# V02.net
KiCad netlist of a schematic drawn in Altium Designer
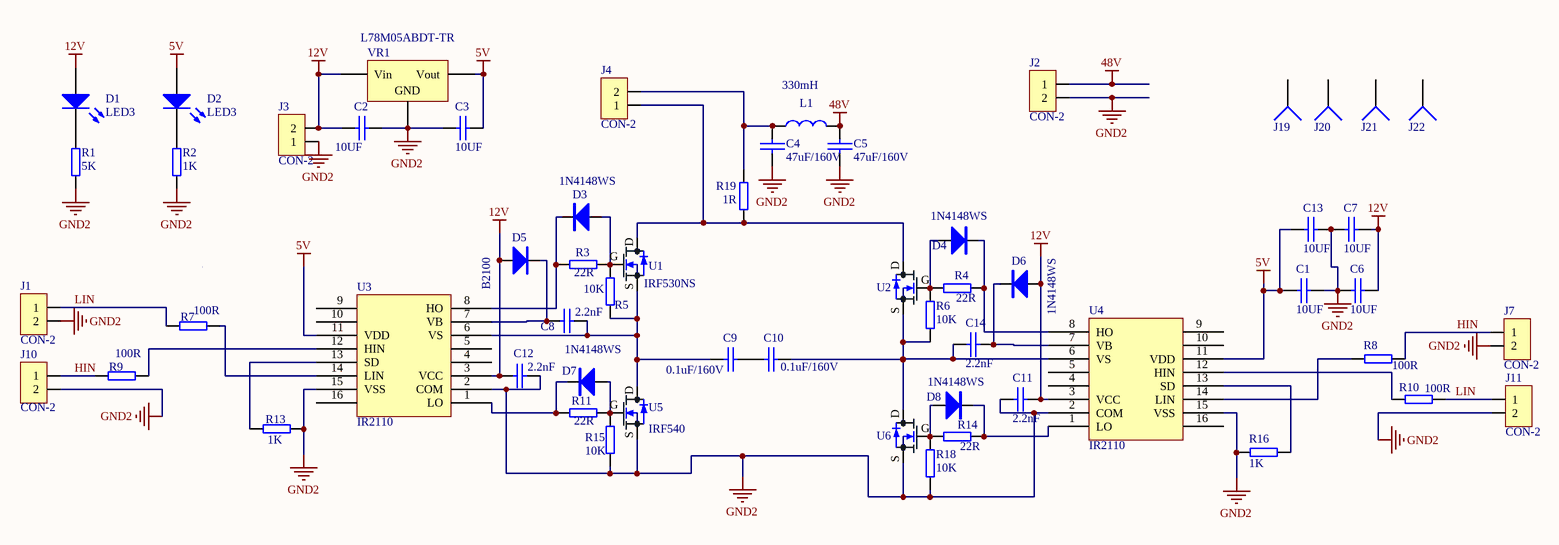
[diagram p0: 发送端V02.SchDoc]

(export (version "E")
  (design (tool "Eeschema 10.0.6"))
  (components
    (comp (ref "C1") (value "10UF") (footprint "1206_C") (libsource (lib "WegeV1") (part "CAP")))
    (comp (ref "C2") (value "10UF") (footprint "1206_C") (libsource (lib "WegeV1") (part "CAP")))
    (comp (ref "C3") (value "10UF") (footprint "1206_C") (libsource (lib "WegeV1") (part "CAP")))
    (comp (ref "C4") (value "47uF/160V") (footprint "C3618") (libsource (lib "WegeV1") (part "CAP")))
    (comp (ref "C5") (value "47uF/160V") (footprint "C3618") (libsource (lib "WegeV1") (part "CAP")))
    (comp (ref "C6") (value "10UF") (footprint "1206_C") (libsource (lib "WegeV1") (part "CAP")))
    (comp (ref "C7") (value "10UF") (footprint "1206_C") (libsource (lib "WegeV1") (part "CAP")))
    (comp (ref "C8") (value "2.2nF") (footprint "1206_C") (libsource (lib "WegeV1") (part "CAP")))
    (comp (ref "C9") (value "0.1uF/160V") (footprint "DSMC82") (libsource (lib "WegeV1") (part "CAP")))
    (comp (ref "C10") (value "0.1uF/160V") (footprint "DSMC82") (libsource (lib "WegeV1") (part "CAP")))
    (comp (ref "C11") (value "2.2nF") (footprint "1206_C") (libsource (lib "WegeV1") (part "CAP")))
    (comp (ref "C12") (value "2.2nF") (footprint "1206_C") (libsource (lib "WegeV1") (part "CAP")))
    (comp (ref "C13") (value "10UF") (footprint "1206_C") (libsource (lib "WegeV1") (part "CAP")))
    (comp (ref "C14") (value "2.2nF") (footprint "1206_C") (libsource (lib "WegeV1") (part "CAP")))
    (comp (ref "D1")
      (value "LED3")
      (footprint "1206_R")
      (description "Typical BLUE SiC LED")
      (fields (field (name "PUBLISHER") "Altium Limited"))
      (libsource (lib "Miscellaneous Devices") (part "LED3"))
    )
    (comp (ref "D2")
      (value "LED3")
      (footprint "1206_R")
      (description "Typical BLUE SiC LED")
      (fields (field (name "PUBLISHER") "Altium Limited"))
      (libsource (lib "Miscellaneous Devices") (part "LED3"))
    )
    (comp (ref "D3")
      (value "1N4148WS")
      (footprint "SOD-123")
      (description "1N4148WS IN4148 0805 SOD323 丝印T4 贴片开关二极管")
      (libsource (lib "WegeV1") (part "1N4148"))
    )
    (comp (ref "D4")
      (value "1N4148WS")
      (footprint "SOD-123")
      (description "1N4148WS IN4148 0805 SOD323 丝印T4 贴片开关二极管")
      (libsource (lib "WegeV1") (part "1N4148"))
    )
    (comp (ref "D5")
      (value "B2100")
      (footprint "1206_R")
      (description "1N4148WS IN4148 0805 SOD323 丝印T4 贴片开关二极管")
      (libsource (lib "WegeV1") (part "1N4148"))
    )
    (comp (ref "D6")
      (value "1N4148WS")
      (footprint "1206_R")
      (description "1N4148WS IN4148 0805 SOD323 丝印T4 贴片开关二极管")
      (libsource (lib "WegeV1") (part "1N4148"))
    )
    (comp (ref "D7")
      (value "1N4148WS")
      (footprint "SOD-123")
      (description "1N4148WS IN4148 0805 SOD323 丝印T4 贴片开关二极管")
      (libsource (lib "WegeV1") (part "1N4148"))
    )
    (comp (ref "D8")
      (value "1N4148WS")
      (footprint "SOD-123")
      (description "1N4148WS IN4148 0805 SOD323 丝印T4 贴片开关二极管")
      (libsource (lib "WegeV1") (part "1N4148"))
    )
    (comp (ref "J1") (value "CON-2") (footprint "GPSPIN") (libsource (lib "") (part "CON-2_2")))
    (comp (ref "J2") (value "CON-2") (footprint "F396P2-1") (libsource (lib "") (part "CON-2_2")))
    (comp (ref "J3") (value "CON-2") (footprint "F396P2-1") (libsource (lib "WegeV1") (part "CON-2")))
    (comp (ref "J4") (value "CON-2") (footprint "HDR1X2") (libsource (lib "WegeV1") (part "CON-2")))
    (comp (ref "J7") (value "CON-2") (footprint "GPSPIN") (libsource (lib "") (part "CON-2_1")))
    (comp (ref "J10") (value "CON-2") (footprint "GPSPIN") (libsource (lib "") (part "CON-2_2")))
    (comp (ref "J11") (value "CON-2") (footprint "GPSPIN") (libsource (lib "") (part "CON-2_1")))
    (comp (ref "J19")
      (value "Socket")
      (footprint "M3")
      (fields (field (name "PUBLISHER") "Altium Limited"))
      (libsource (lib "Miscellaneous Connectors") (part "Socket"))
    )
    (comp (ref "J20")
      (value "Socket")
      (footprint "M3")
      (fields (field (name "PUBLISHER") "Altium Limited"))
      (libsource (lib "Miscellaneous Connectors") (part "Socket"))
    )
    (comp (ref "J21")
      (value "Socket")
      (footprint "M3")
      (fields (field (name "PUBLISHER") "Altium Limited"))
      (libsource (lib "Miscellaneous Connectors") (part "Socket"))
    )
    (comp (ref "J22")
      (value "Socket")
      (footprint "M3")
      (fields (field (name "PUBLISHER") "Altium Limited"))
      (libsource (lib "Miscellaneous Connectors") (part "Socket"))
    )
    (comp (ref "L1")
      (value "330mH")
      (footprint "H3.3")
      (description "CD75--2.2mH 222M 贴片功率电感绕线功率电感 7*7.8*5mm")
      (libsource (lib "WegeV1") (part "INL"))
    )
    (comp (ref "R1") (value "5K") (footprint "1206_R") (libsource (lib "WegeV1") (part "RES")))
    (comp (ref "R2") (value "1K") (footprint "1206_R") (libsource (lib "WegeV1") (part "RES")))
    (comp (ref "R3") (value "22R") (footprint "1206_R") (libsource (lib "WegeV1") (part "RES")))
    (comp (ref "R4") (value "22R") (footprint "1206_R") (libsource (lib "WegeV1") (part "RES")))
    (comp (ref "R5") (value "10K") (footprint "1206_R") (libsource (lib "WegeV1") (part "RES")))
    (comp (ref "R6") (value "10K") (footprint "1206_R") (libsource (lib "WegeV1") (part "RES")))
    (comp (ref "R7") (value "100R") (footprint "1206_R") (libsource (lib "WegeV1") (part "RES")))
    (comp (ref "R8") (value "100R") (footprint "1206_R") (libsource (lib "WegeV1") (part "RES")))
    (comp (ref "R9") (value "100R") (footprint "1206_R") (libsource (lib "WegeV1") (part "RES")))
    (comp (ref "R10") (value "100R") (footprint "1206_R") (libsource (lib "WegeV1") (part "RES")))
    (comp (ref "R11") (value "22R") (footprint "1206_R") (libsource (lib "WegeV1") (part "RES")))
    (comp (ref "R13") (value "1K") (footprint "1206_R") (libsource (lib "WegeV1") (part "RES")))
    (comp (ref "R14") (value "22R") (footprint "1206_R") (libsource (lib "WegeV1") (part "RES")))
    (comp (ref "R15") (value "10K") (footprint "1206_R") (libsource (lib "WegeV1") (part "RES")))
    (comp (ref "R16") (value "1K") (footprint "1206_R") (libsource (lib "WegeV1") (part "RES")))
    (comp (ref "R18") (value "10K") (footprint "1206_R") (libsource (lib "WegeV1") (part "RES")))
    (comp (ref "R19") (value "1R") (footprint "R10MR10MM1D5") (libsource (lib "WegeV1") (part "RES")))
    (comp (ref "U1") (value "IRF530NS") (footprint "TO-220") (libsource (lib "WegeV1") (part "NMOS")))
    (comp (ref "U2") (value "NMOS") (footprint "TO-220") (libsource (lib "WegeV1") (part "NMOS")))
    (comp (ref "U3")
      (value "IR2110")
      (footprint "SOIC-16_300mil")
      (libsource (lib "IC_temp") (part "IR2110"))
    )
    (comp (ref "U4") (value "IR2110") (footprint "SOIC-16_300mil") (libsource (lib "") (part "IR2110_1")))
    (comp (ref "U5") (value "IRF540") (footprint "TO-220") (libsource (lib "WegeV1") (part "NMOS")))
    (comp (ref "U6") (value "NMOS") (footprint "TO-220") (libsource (lib "WegeV1") (part "NMOS")))
    (comp (ref "VR1")
      (value "L78M05ABDT-TR")
      (footprint "TO-252-2-180")
      (description "低压差线性稳压(LDO)")
      (libsource (lib "Miscellaneous Devices LC") (part "TO-252-2 L78M05ABDT-TR"))
    )
  )
  (nets
    (net (code "1") (name "/HIN") (class "Default")
      (node (ref "J10") (pin "1") (pinfunction "1_1") (pintype "passive"))
      (node (ref "J7") (pin "1") (pinfunction "1_1") (pintype "passive"))
      (node (ref "R8") (pin "1") (pinfunction "1_1") (pintype "passive"))
      (node (ref "R9") (pin "1") (pinfunction "1_1") (pintype "passive"))
    )
    (net (code "2") (name "/LIN") (class "Default")
      (node (ref "J1") (pin "1") (pinfunction "1_1") (pintype "passive"))
      (node (ref "J11") (pin "1") (pinfunction "1_1") (pintype "passive"))
      (node (ref "R10") (pin "1") (pinfunction "1_1") (pintype "passive"))
      (node (ref "R7") (pin "1") (pinfunction "1_1") (pintype "passive"))
    )
    (net (code "3") (name "5V") (class "Default")
      (node (ref "C1") (pin "1") (pinfunction "1_1") (pintype "passive"))
      (node (ref "C13") (pin "1") (pinfunction "1_1") (pintype "passive"))
      (node (ref "C3") (pin "1") (pinfunction "1_1") (pintype "passive"))
      (node (ref "D2") (pin "1") (pinfunction "A_1") (pintype "passive"))
      (node (ref "U3") (pin "11") (pinfunction "VDD_11") (pintype "passive"))
      (node (ref "U4") (pin "11") (pinfunction "VDD_11") (pintype "passive"))
      (node (ref "VR1") (pin "3") (pinfunction "Vout_3") (pintype "passive"))
    )
    (net (code "4") (name "12V") (class "Default")
      (node (ref "C11") (pin "2") (pinfunction "2_2") (pintype "passive"))
      (node (ref "C12") (pin "2") (pinfunction "2_2") (pintype "passive"))
      (node (ref "C2") (pin "2") (pinfunction "2_2") (pintype "passive"))
      (node (ref "C6") (pin "2") (pinfunction "2_2") (pintype "passive"))
      (node (ref "C7") (pin "2") (pinfunction "2_2") (pintype "passive"))
      (node (ref "D1") (pin "1") (pinfunction "A_1") (pintype "passive"))
      (node (ref "D5") (pin "1") (pinfunction "A_1") (pintype "passive"))
      (node (ref "D6") (pin "1") (pinfunction "A_1") (pintype "passive"))
      (node (ref "J3") (pin "2") (pinfunction "2_2") (pintype "passive"))
      (node (ref "U3") (pin "3") (pinfunction "VCC_3") (pintype "passive"))
      (node (ref "U4") (pin "3") (pinfunction "VCC_3") (pintype "passive"))
      (node (ref "VR1") (pin "1") (pinfunction "Vin_1") (pintype "passive"))
    )
    (net (code "5") (name "48V") (class "Default")
      (node (ref "C5") (pin "1") (pinfunction "1_1") (pintype "passive"))
      (node (ref "J2") (pin "1") (pinfunction "1_1") (pintype "passive"))
      (node (ref "L1") (pin "1") (pinfunction "1_1") (pintype "passive"))
    )
    (net (code "6") (name "GND2") (class "Default")
      (node (ref "C1") (pin "2") (pinfunction "2_2") (pintype "passive"))
      (node (ref "C11") (pin "1") (pinfunction "1_1") (pintype "passive"))
      (node (ref "C12") (pin "1") (pinfunction "1_1") (pintype "passive"))
      (node (ref "C13") (pin "2") (pinfunction "2_2") (pintype "passive"))
      (node (ref "C2") (pin "1") (pinfunction "1_1") (pintype "passive"))
      (node (ref "C3") (pin "2") (pinfunction "2_2") (pintype "passive"))
      (node (ref "C4") (pin "2") (pinfunction "2_2") (pintype "passive"))
      (node (ref "C5") (pin "2") (pinfunction "2_2") (pintype "passive"))
      (node (ref "C6") (pin "1") (pinfunction "1_1") (pintype "passive"))
      (node (ref "C7") (pin "1") (pinfunction "1_1") (pintype "passive"))
      (node (ref "J1") (pin "2") (pinfunction "2_2") (pintype "passive"))
      (node (ref "J10") (pin "2") (pinfunction "2_2") (pintype "passive"))
      (node (ref "J11") (pin "2") (pinfunction "2_2") (pintype "passive"))
      (node (ref "J2") (pin "2") (pinfunction "2_2") (pintype "passive"))
      (node (ref "J3") (pin "1") (pinfunction "1_1") (pintype "passive"))
      (node (ref "J7") (pin "2") (pinfunction "2_2") (pintype "passive"))
      (node (ref "R1") (pin "1") (pinfunction "1_1") (pintype "passive"))
      (node (ref "R13") (pin "2") (pinfunction "2_2") (pintype "passive"))
      (node (ref "R15") (pin "1") (pinfunction "1_1") (pintype "passive"))
      (node (ref "R16") (pin "2") (pinfunction "2_2") (pintype "passive"))
      (node (ref "R18") (pin "1") (pinfunction "1_1") (pintype "passive"))
      (node (ref "R2") (pin "1") (pinfunction "1_1") (pintype "passive"))
      (node (ref "U3") (pin "15") (pinfunction "VSS_15") (pintype "passive"))
      (node (ref "U3") (pin "2") (pinfunction "COM_2") (pintype "passive"))
      (node (ref "U4") (pin "15") (pinfunction "VSS_15") (pintype "passive"))
      (node (ref "U4") (pin "2") (pinfunction "COM_2") (pintype "passive"))
      (node (ref "U5") (pin "S") (pinfunction "S_S") (pintype "passive"))
      (node (ref "U6") (pin "S") (pinfunction "S_S") (pintype "passive"))
      (node (ref "VR1") (pin "2") (pinfunction "GND_2") (pintype "passive"))
    )
    (net (code "7") (name "Net-(C4-Pad1)") (class "Default")
      (node (ref "C4") (pin "1") (pinfunction "1_1") (pintype "passive"))
      (node (ref "J4") (pin "2") (pinfunction "2_2") (pintype "passive"))
      (node (ref "L1") (pin "2") (pinfunction "2_2") (pintype "passive"))
      (node (ref "R19") (pin "2") (pinfunction "2_2") (pintype "passive"))
    )
    (net (code "8") (name "Net-(C10-Pad1)") (class "Default")
      (node (ref "C10") (pin "1") (pinfunction "1_1") (pintype "passive"))
      (node (ref "C9") (pin "2") (pinfunction "2_2") (pintype "passive"))
    )
    (net (code "9") (name "Net-(D1-K)") (class "Default")
      (node (ref "D1") (pin "2") (pinfunction "K_2") (pintype "passive"))
      (node (ref "R1") (pin "2") (pinfunction "2_2") (pintype "passive"))
    )
    (net (code "10") (name "Net-(D2-K)") (class "Default")
      (node (ref "D2") (pin "2") (pinfunction "K_2") (pintype "passive"))
      (node (ref "R2") (pin "2") (pinfunction "2_2") (pintype "passive"))
    )
    (net (code "11") (name "Net-(D3-A)") (class "Default")
      (node (ref "D3") (pin "1") (pinfunction "A_1") (pintype "passive"))
      (node (ref "R3") (pin "2") (pinfunction "2_2") (pintype "passive"))
      (node (ref "R5") (pin "2") (pinfunction "2_2") (pintype "passive"))
      (node (ref "U1") (pin "G") (pinfunction "G_G") (pintype "passive"))
    )
    (net (code "12") (name "Net-(D3-K)") (class "Default")
      (node (ref "D3") (pin "2") (pinfunction "K_2") (pintype "passive"))
      (node (ref "R3") (pin "1") (pinfunction "1_1") (pintype "passive"))
      (node (ref "U3") (pin "8") (pinfunction "HO_8") (pintype "passive"))
    )
    (net (code "13") (name "Net-(D4-A)") (class "Default")
      (node (ref "D4") (pin "1") (pinfunction "A_1") (pintype "passive"))
      (node (ref "R4") (pin "2") (pinfunction "2_2") (pintype "passive"))
      (node (ref "R6") (pin "2") (pinfunction "2_2") (pintype "passive"))
      (node (ref "U2") (pin "G") (pinfunction "G_G") (pintype "passive"))
    )
    (net (code "14") (name "Net-(D4-K)") (class "Default")
      (node (ref "D4") (pin "2") (pinfunction "K_2") (pintype "passive"))
      (node (ref "R4") (pin "1") (pinfunction "1_1") (pintype "passive"))
      (node (ref "U4") (pin "8") (pinfunction "HO_8") (pintype "passive"))
    )
    (net (code "15") (name "Net-(D5-K)") (class "Default")
      (node (ref "C8") (pin "2") (pinfunction "2_2") (pintype "passive"))
      (node (ref "D5") (pin "2") (pinfunction "K_2") (pintype "passive"))
      (node (ref "U3") (pin "7") (pinfunction "VB_7") (pintype "passive"))
    )
    (net (code "16") (name "Net-(D6-K)") (class "Default")
      (node (ref "C14") (pin "2") (pinfunction "2_2") (pintype "passive"))
      (node (ref "D6") (pin "2") (pinfunction "K_2") (pintype "passive"))
      (node (ref "U4") (pin "7") (pinfunction "VB_7") (pintype "passive"))
    )
    (net (code "17") (name "Net-(D7-A)") (class "Default")
      (node (ref "D7") (pin "1") (pinfunction "A_1") (pintype "passive"))
      (node (ref "R11") (pin "2") (pinfunction "2_2") (pintype "passive"))
      (node (ref "R15") (pin "2") (pinfunction "2_2") (pintype "passive"))
      (node (ref "U5") (pin "G") (pinfunction "G_G") (pintype "passive"))
    )
    (net (code "18") (name "Net-(D7-K)") (class "Default")
      (node (ref "D7") (pin "2") (pinfunction "K_2") (pintype "passive"))
      (node (ref "R11") (pin "1") (pinfunction "1_1") (pintype "passive"))
      (node (ref "U3") (pin "1") (pinfunction "LO_1") (pintype "passive"))
    )
    (net (code "19") (name "Net-(D8-A)") (class "Default")
      (node (ref "D8") (pin "1") (pinfunction "A_1") (pintype "passive"))
      (node (ref "R14") (pin "2") (pinfunction "2_2") (pintype "passive"))
      (node (ref "R18") (pin "2") (pinfunction "2_2") (pintype "passive"))
      (node (ref "U6") (pin "G") (pinfunction "G_G") (pintype "passive"))
    )
    (net (code "20") (name "Net-(D8-K)") (class "Default")
      (node (ref "D8") (pin "2") (pinfunction "K_2") (pintype "passive"))
      (node (ref "R14") (pin "1") (pinfunction "1_1") (pintype "passive"))
      (node (ref "U4") (pin "1") (pinfunction "LO_1") (pintype "passive"))
    )
    (net (code "21") (name "Net-(J4-Pad1)") (class "Default")
      (node (ref "J4") (pin "1") (pinfunction "1_1") (pintype "passive"))
      (node (ref "R19") (pin "1") (pinfunction "1_1") (pintype "passive"))
      (node (ref "U1") (pin "D") (pinfunction "D_D") (pintype "passive"))
      (node (ref "U2") (pin "D") (pinfunction "D_D") (pintype "passive"))
    )
    (net (code "22") (name "Net-(U3-HIN)") (class "Default")
      (node (ref "R9") (pin "2") (pinfunction "2_2") (pintype "passive"))
      (node (ref "U3") (pin "12") (pinfunction "HIN_12") (pintype "passive"))
    )
    (net (code "23") (name "Net-(U3-LIN)") (class "Default")
      (node (ref "R7") (pin "2") (pinfunction "2_2") (pintype "passive"))
      (node (ref "U3") (pin "14") (pinfunction "LIN_14") (pintype "passive"))
    )
    (net (code "24") (name "Net-(U3-SD)") (class "Default")
      (node (ref "R13") (pin "1") (pinfunction "1_1") (pintype "passive"))
      (node (ref "U3") (pin "13") (pinfunction "SD_13") (pintype "passive"))
    )
    (net (code "25") (name "Net-(U3-VS)") (class "Default")
      (node (ref "C8") (pin "1") (pinfunction "1_1") (pintype "passive"))
      (node (ref "C9") (pin "1") (pinfunction "1_1") (pintype "passive"))
      (node (ref "R5") (pin "1") (pinfunction "1_1") (pintype "passive"))
      (node (ref "U1") (pin "S") (pinfunction "S_S") (pintype "passive"))
      (node (ref "U3") (pin "6") (pinfunction "VS_6") (pintype "passive"))
      (node (ref "U5") (pin "D") (pinfunction "D_D") (pintype "passive"))
    )
    (net (code "26") (name "Net-(U4-HIN)") (class "Default")
      (node (ref "R10") (pin "2") (pinfunction "2_2") (pintype "passive"))
      (node (ref "U4") (pin "12") (pinfunction "HIN_12") (pintype "passive"))
    )
    (net (code "27") (name "Net-(U4-LIN)") (class "Default")
      (node (ref "R8") (pin "2") (pinfunction "2_2") (pintype "passive"))
      (node (ref "U4") (pin "14") (pinfunction "LIN_14") (pintype "passive"))
    )
    (net (code "28") (name "Net-(U4-SD)") (class "Default")
      (node (ref "R16") (pin "1") (pinfunction "1_1") (pintype "passive"))
      (node (ref "U4") (pin "13") (pinfunction "SD_13") (pintype "passive"))
    )
    (net (code "29") (name "Net-(U4-VS)") (class "Default")
      (node (ref "C10") (pin "2") (pinfunction "2_2") (pintype "passive"))
      (node (ref "C14") (pin "1") (pinfunction "1_1") (pintype "passive"))
      (node (ref "R6") (pin "1") (pinfunction "1_1") (pintype "passive"))
      (node (ref "U2") (pin "S") (pinfunction "S_S") (pintype "passive"))
      (node (ref "U4") (pin "6") (pinfunction "VS_6") (pintype "passive"))
      (node (ref "U6") (pin "D") (pinfunction "D_D") (pintype "passive"))
    )
    (net (code "30") (name "unconnected-(J19-Pad1)") (class "Default")
      (node (ref "J19") (pin "1") (pinfunction "1_1") (pintype "passive"))
    )
    (net (code "31") (name "unconnected-(J20-Pad1)") (class "Default")
      (node (ref "J20") (pin "1") (pinfunction "1_1") (pintype "passive"))
    )
    (net (code "32") (name "unconnected-(J21-Pad1)") (class "Default")
      (node (ref "J21") (pin "1") (pinfunction "1_1") (pintype "passive"))
    )
    (net (code "33") (name "unconnected-(J22-Pad1)") (class "Default")
      (node (ref "J22") (pin "1") (pinfunction "1_1") (pintype "passive"))
    )
    (net (code "34") (name "unconnected-(U3-Pad4)") (class "Default")
      (node (ref "U3") (pin "4") (pintype "passive"))
    )
    (net (code "35") (name "unconnected-(U3-Pad5)") (class "Default")
      (node (ref "U3") (pin "5") (pintype "passive"))
    )
    (net (code "36") (name "unconnected-(U3-Pad9)") (class "Default")
      (node (ref "U3") (pin "9") (pintype "passive"))
    )
    (net (code "37") (name "unconnected-(U3-Pad10)") (class "Default")
      (node (ref "U3") (pin "10") (pintype "passive"))
    )
    (net (code "38") (name "unconnected-(U3-Pad16)") (class "Default")
      (node (ref "U3") (pin "16") (pintype "passive"))
    )
    (net (code "39") (name "unconnected-(U4-Pad4)") (class "Default")
      (node (ref "U4") (pin "4") (pintype "passive"))
    )
    (net (code "40") (name "unconnected-(U4-Pad5)") (class "Default")
      (node (ref "U4") (pin "5") (pintype "passive"))
    )
    (net (code "41") (name "unconnected-(U4-Pad9)") (class "Default")
      (node (ref "U4") (pin "9") (pintype "passive"))
    )
    (net (code "42") (name "unconnected-(U4-Pad10)") (class "Default")
      (node (ref "U4") (pin "10") (pintype "passive"))
    )
    (net (code "43") (name "unconnected-(U4-Pad16)") (class "Default")
      (node (ref "U4") (pin "16") (pintype "passive"))
    )
  )
)
